# ProPrj_8_29_2025-09-02.net
KiCad netlist of a schematic drawn in EasyEDA Pro
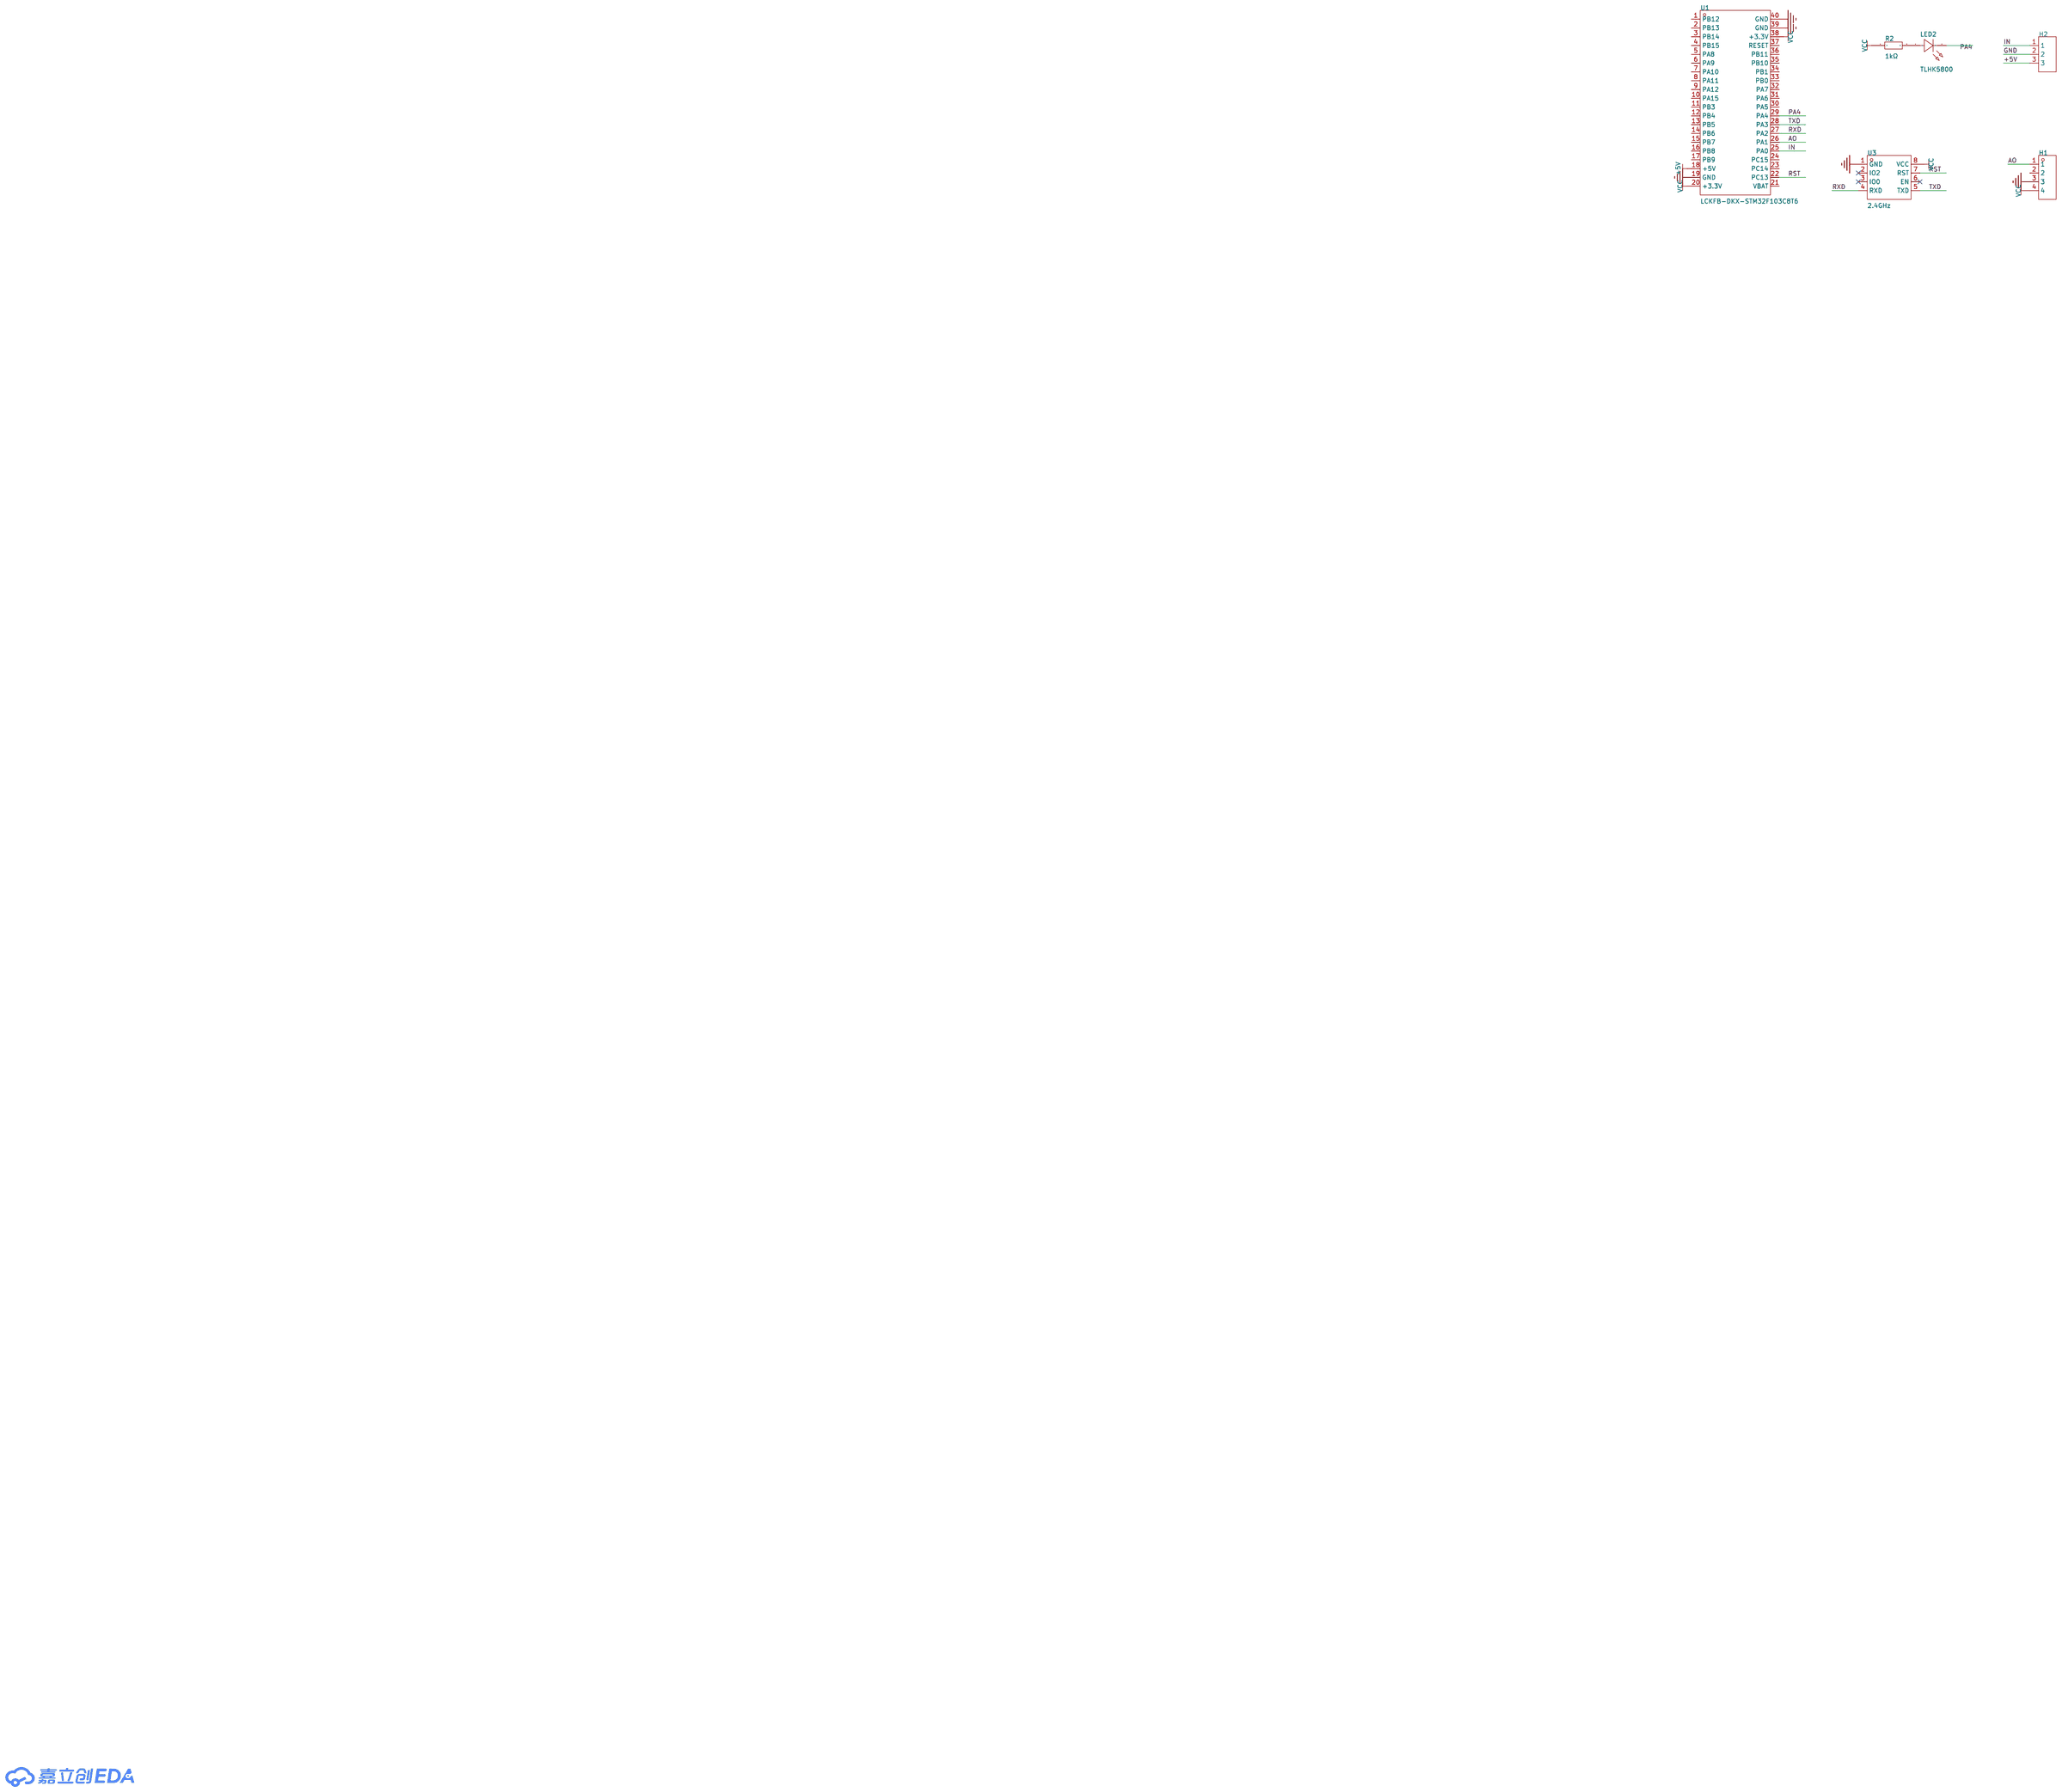
[diagram p0: schematic sheet]

(export (version "E")
  (design (tool "Eeschema 10.0.6"))
  (components
    (comp (ref "H1")
      (value "~")
      (footprint "easyedapro:HDR-TH_4P-P2.54-V-F")
      (libsource (lib "easyedapro") (part "2.54-1*4P母"))
    )
    (comp (ref "H2")
      (value "~")
      (footprint "easyedapro:HDR-TH_3P-P2.54-V-F")
      (libsource (lib "easyedapro") (part "PM254V-11-03-H85"))
    )
    (comp (ref "LED2")
      (value "TLHK5800")
      (footprint "easyedapro:LED-TH_BD5.0-P2.54-RD")
      (fields (field (name "Manufacturer") "VISHAY(威世)"))
      (libsource (lib "easyedapro") (part "TLHK5800"))
    )
    (comp (ref "R2")
      (value "1kΩ")
      (footprint "easyedapro:RES-TH_BD2.5-L6.5-P10.50-D0.6")
      (description "电阻类型:金属膜电阻;阻值:1kΩ;精度:±1%;功率:250mW;温度系数:±50ppm/°C;")
      (fields
        (field (name "Manufacturer Part") "MFR0W4F1001A50")
        (field (name "Manufacturer") "UNI-ROYAL(厚声)")
      )
      (libsource (lib "easyedapro") (part "MFR0W4F1001A50"))
    )
    (comp (ref "U1")
      (value "LCKFB-DKX-STM32F103C8T6")
      (footprint "easyedapro:CONN-TH_L53.3-W22.9_STM32F103C8T6-CARD")
      (fields (field (name "Manufacturer") "立创开发板"))
      (libsource (lib "easyedapro") (part "LCKFB-DKX-STM32F103C8T6"))
    )
    (comp (ref "U3")
      (value "2.4GHz")
      (footprint "easyedapro:WIFIM-TH_8P-L24.7-W14.4-P2.54")
      (description "核心处理器:ESP8266芯片;频率:2.4GHz;天线形式:板载PCB天线;发射功率:16dBm;接收灵敏度:-90dBm;")
      (fields (field (name "Manufacturer Part") "ESP-01S") (field (name "Manufacturer") "Ai-Thinker(安信可)"))
      (libsource (lib "easyedapro") (part "ESP-01S_C503582"))
    )
  )
  (nets
    (net (code "1") (name "+5V") (class "Default")
      (node (ref "H2") (pin "3") (pinfunction "3_3") (pintype "unspecified"))
      (node (ref "U1") (pin "18") (pinfunction "+5V_18") (pintype "unspecified"))
    )
    (net (code "2") (name "/AO") (class "Default")
      (node (ref "H1") (pin "1") (pinfunction "1_1") (pintype "unspecified"))
      (node (ref "U1") (pin "26") (pinfunction "PA1_26") (pintype "unspecified"))
    )
    (net (code "3") (name "/IN") (class "Default")
      (node (ref "H2") (pin "1") (pinfunction "1_1") (pintype "unspecified"))
      (node (ref "U1") (pin "25") (pinfunction "PA0_25") (pintype "unspecified"))
    )
    (net (code "4") (name "/PA4") (class "Default")
      (node (ref "LED2") (pin "2") (pinfunction "K_2") (pintype "unspecified"))
      (node (ref "U1") (pin "29") (pinfunction "PA4_29") (pintype "unspecified"))
    )
    (net (code "5") (name "/RST") (class "Default")
      (node (ref "U1") (pin "22") (pinfunction "PC13_22") (pintype "unspecified"))
      (node (ref "U3") (pin "7") (pinfunction "RST_7") (pintype "unspecified"))
    )
    (net (code "6") (name "/RXD") (class "Default")
      (node (ref "U1") (pin "27") (pinfunction "PA2_27") (pintype "unspecified"))
      (node (ref "U3") (pin "4") (pinfunction "RXD_4") (pintype "unspecified"))
    )
    (net (code "7") (name "/TXD") (class "Default")
      (node (ref "U1") (pin "28") (pinfunction "PA3_28") (pintype "unspecified"))
      (node (ref "U3") (pin "5") (pinfunction "TXD_5") (pintype "unspecified"))
    )
    (net (code "8") (name "GND") (class "Default")
      (node (ref "H1") (pin "3") (pinfunction "3_3") (pintype "unspecified"))
      (node (ref "H2") (pin "2") (pinfunction "2_2") (pintype "unspecified"))
      (node (ref "U1") (pin "19") (pinfunction "GND_19") (pintype "unspecified"))
      (node (ref "U1") (pin "39") (pinfunction "GND_39") (pintype "unspecified"))
      (node (ref "U1") (pin "40") (pinfunction "GND_40") (pintype "unspecified"))
      (node (ref "U3") (pin "1") (pinfunction "GND_1") (pintype "unspecified"))
    )
    (net (code "9") (name "Net-(LED2-A)") (class "Default")
      (node (ref "LED2") (pin "1") (pinfunction "A_1") (pintype "unspecified"))
      (node (ref "R2") (pin "2") (pinfunction "2_2") (pintype "input"))
    )
    (net (code "10") (name "VCC") (class "Default")
      (node (ref "H1") (pin "4") (pinfunction "4_4") (pintype "unspecified"))
      (node (ref "R2") (pin "1") (pinfunction "1_1") (pintype "input"))
      (node (ref "U1") (pin "20") (pinfunction "+3.3V_20") (pintype "unspecified"))
      (node (ref "U1") (pin "38") (pinfunction "+3.3V_38") (pintype "unspecified"))
      (node (ref "U3") (pin "8") (pinfunction "VCC_8") (pintype "unspecified"))
    )
    (net (code "11") (name "unconnected-(H1-Pad2)") (class "Default")
      (node (ref "H1") (pin "2") (pinfunction "2_2") (pintype "unspecified"))
    )
    (net (code "12") (name "unconnected-(U1-PA5-Pad30)") (class "Default")
      (node (ref "U1") (pin "30") (pinfunction "PA5_30") (pintype "unspecified"))
    )
    (net (code "13") (name "unconnected-(U1-PA6-Pad31)") (class "Default")
      (node (ref "U1") (pin "31") (pinfunction "PA6_31") (pintype "unspecified"))
    )
    (net (code "14") (name "unconnected-(U1-PA7-Pad32)") (class "Default")
      (node (ref "U1") (pin "32") (pinfunction "PA7_32") (pintype "unspecified"))
    )
    (net (code "15") (name "unconnected-(U1-PA8-Pad5)") (class "Default")
      (node (ref "U1") (pin "5") (pinfunction "PA8_5") (pintype "unspecified"))
    )
    (net (code "16") (name "unconnected-(U1-PA9-Pad6)") (class "Default")
      (node (ref "U1") (pin "6") (pinfunction "PA9_6") (pintype "unspecified"))
    )
    (net (code "17") (name "unconnected-(U1-PA10-Pad7)") (class "Default")
      (node (ref "U1") (pin "7") (pinfunction "PA10_7") (pintype "unspecified"))
    )
    (net (code "18") (name "unconnected-(U1-PA11-Pad8)") (class "Default")
      (node (ref "U1") (pin "8") (pinfunction "PA11_8") (pintype "unspecified"))
    )
    (net (code "19") (name "unconnected-(U1-PA12-Pad9)") (class "Default")
      (node (ref "U1") (pin "9") (pinfunction "PA12_9") (pintype "unspecified"))
    )
    (net (code "20") (name "unconnected-(U1-PA15-Pad10)") (class "Default")
      (node (ref "U1") (pin "10") (pinfunction "PA15_10") (pintype "unspecified"))
    )
    (net (code "21") (name "unconnected-(U1-PB0-Pad33)") (class "Default")
      (node (ref "U1") (pin "33") (pinfunction "PB0_33") (pintype "unspecified"))
    )
    (net (code "22") (name "unconnected-(U1-PB1-Pad34)") (class "Default")
      (node (ref "U1") (pin "34") (pinfunction "PB1_34") (pintype "unspecified"))
    )
    (net (code "23") (name "unconnected-(U1-PB3-Pad11)") (class "Default")
      (node (ref "U1") (pin "11") (pinfunction "PB3_11") (pintype "unspecified"))
    )
    (net (code "24") (name "unconnected-(U1-PB4-Pad12)") (class "Default")
      (node (ref "U1") (pin "12") (pinfunction "PB4_12") (pintype "unspecified"))
    )
    (net (code "25") (name "unconnected-(U1-PB5-Pad13)") (class "Default")
      (node (ref "U1") (pin "13") (pinfunction "PB5_13") (pintype "unspecified"))
    )
    (net (code "26") (name "unconnected-(U1-PB6-Pad14)") (class "Default")
      (node (ref "U1") (pin "14") (pinfunction "PB6_14") (pintype "unspecified"))
    )
    (net (code "27") (name "unconnected-(U1-PB7-Pad15)") (class "Default")
      (node (ref "U1") (pin "15") (pinfunction "PB7_15") (pintype "unspecified"))
    )
    (net (code "28") (name "unconnected-(U1-PB8-Pad16)") (class "Default")
      (node (ref "U1") (pin "16") (pinfunction "PB8_16") (pintype "unspecified"))
    )
    (net (code "29") (name "unconnected-(U1-PB9-Pad17)") (class "Default")
      (node (ref "U1") (pin "17") (pinfunction "PB9_17") (pintype "unspecified"))
    )
    (net (code "30") (name "unconnected-(U1-PB10-Pad35)") (class "Default")
      (node (ref "U1") (pin "35") (pinfunction "PB10_35") (pintype "unspecified"))
    )
    (net (code "31") (name "unconnected-(U1-PB11-Pad36)") (class "Default")
      (node (ref "U1") (pin "36") (pinfunction "PB11_36") (pintype "unspecified"))
    )
    (net (code "32") (name "unconnected-(U1-PB12-Pad1)") (class "Default")
      (node (ref "U1") (pin "1") (pinfunction "PB12_1") (pintype "unspecified"))
    )
    (net (code "33") (name "unconnected-(U1-PB13-Pad2)") (class "Default")
      (node (ref "U1") (pin "2") (pinfunction "PB13_2") (pintype "unspecified"))
    )
    (net (code "34") (name "unconnected-(U1-PB14-Pad3)") (class "Default")
      (node (ref "U1") (pin "3") (pinfunction "PB14_3") (pintype "unspecified"))
    )
    (net (code "35") (name "unconnected-(U1-PB15-Pad4)") (class "Default")
      (node (ref "U1") (pin "4") (pinfunction "PB15_4") (pintype "unspecified"))
    )
    (net (code "36") (name "unconnected-(U1-PC14-Pad23)") (class "Default")
      (node (ref "U1") (pin "23") (pinfunction "PC14_23") (pintype "unspecified"))
    )
    (net (code "37") (name "unconnected-(U1-PC15-Pad24)") (class "Default")
      (node (ref "U1") (pin "24") (pinfunction "PC15_24") (pintype "unspecified"))
    )
    (net (code "38") (name "unconnected-(U1-RESET-Pad37)") (class "Default")
      (node (ref "U1") (pin "37") (pinfunction "RESET_37") (pintype "unspecified"))
    )
    (net (code "39") (name "unconnected-(U1-VBAT-Pad21)") (class "Default")
      (node (ref "U1") (pin "21") (pinfunction "VBAT_21") (pintype "unspecified"))
    )
    (net (code "40") (name "unconnected-(U3-EN-Pad6)") (class "Default")
      (node (ref "U3") (pin "6") (pinfunction "EN_6") (pintype "unspecified+no_connect"))
    )
    (net (code "41") (name "unconnected-(U3-IO0-Pad3)") (class "Default")
      (node (ref "U3") (pin "3") (pinfunction "IO0_3") (pintype "unspecified+no_connect"))
    )
    (net (code "42") (name "unconnected-(U3-IO2-Pad2)") (class "Default")
      (node (ref "U3") (pin "2") (pinfunction "IO2_2") (pintype "unspecified+no_connect"))
    )
  )
)
